# 04_MCU.net
KiCad netlist of a schematic drawn in Altium Designer
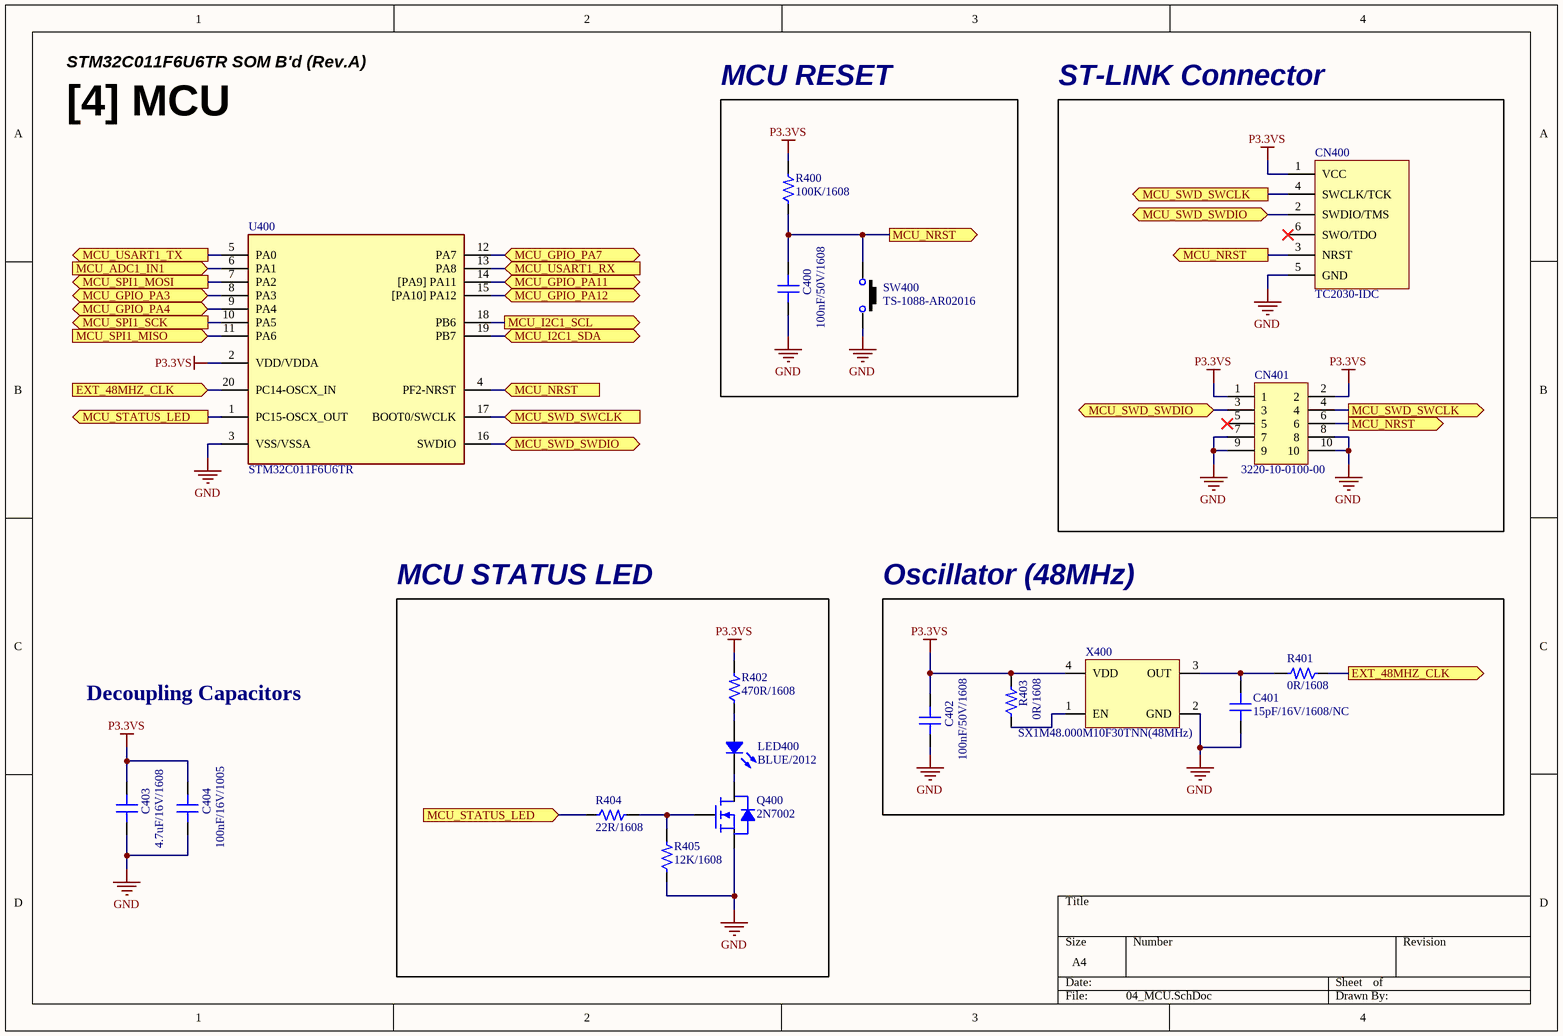
[diagram p0: 04_MCU.SchDoc]

(export (version "E")
  (design (tool "Eeschema 10.0.6"))
  (components
    (comp (ref "C400")
      (value "100nF/50V/1608")
      (footprint "CAP 1608 (0603_INCH)")
      (description "Ceramic CAP_100nF/50V/1608")
      (fields (field (name "LCSC PART #") "C14663"))
      (libsource (lib "Arkx") (part "CAP_100nF/50V/1608"))
    )
    (comp (ref "C401")
      (value "15pF/16V/1608/NC")
      (footprint "CAP 1608 (0603_INCH)/NC")
      (description "Ceramic CAP_15pF/16V/1608")
      (libsource (lib "Arkx") (part "CAP_NC_15pF/16V/1608"))
    )
    (comp (ref "C402")
      (value "100nF/50V/1608")
      (footprint "CAP 1608 (0603_INCH)")
      (description "Ceramic CAP_100nF/50V/1608")
      (fields (field (name "LCSC PART #") "C14663"))
      (libsource (lib "Arkx") (part "CAP_100nF/50V/1608"))
    )
    (comp (ref "C403")
      (value "4.7uF/16V/1608")
      (footprint "CAP 1608 (0603_INCH)")
      (description "Ceramic CAP_4.7uF/16V/1608")
      (fields (field (name "LCSC PART #") "C19666"))
      (libsource (lib "Arkx") (part "CAP_4.7uF/16V/1608"))
    )
    (comp (ref "C404")
      (value "100nF/16V/1005")
      (footprint "CAP 1005 (0402_INCH)")
      (description "Ceramic CAP_100nF/16V/1005")
      (fields (field (name "LCSC PART #") "C1525"))
      (libsource (lib "Arkx") (part "CAP_100nF/16V/1005"))
    )
    (comp (ref "CN400")
      (value "TC2030-IDC")
      (footprint "CON_TC2030-FP")
      (description "Tag-Connect No-Solder SWD Debug Connector DO NOT PLACE")
      (fields (field (name "MANUFACTURER") "Tag-Connect") (field (name "MANUFACTURER PART NUMBER") "TC2030"))
      (libsource (lib "Arkx") (part "CON_TC2030-IDC"))
    )
    (comp (ref "CN401")
      (value "3220-10-0100-00")
      (footprint "CON 3220-10-0100-00 (Hand_Solder)")
      (description "CONN HEADER VERT 10POS 1.27MM")
      (libsource (lib "Arkx") (part "CON_IDC_3220-10-0100-00"))
    )
    (comp (ref "LED400")
      (value "BLUE/2012")
      (footprint "LED MHT170RGBCT (BLUE)")
      (fields (field (name "LCSC PART #") "C2962094"))
      (libsource (lib "Arkx") (part "LED_MHT170RGBCT(BLUE)"))
    )
    (comp (ref "Q400")
      (value "2N7002")
      (footprint "SOT 23-3 (DIODES INCORPORATED)")
      (description "60V 115mA 200mW 7.5Ω@10V,500mA N Channel SOT-23  MOSFETs ROHS")
      (fields (field (name "LCSC PART #") "C8545"))
      (libsource (lib "Arkx") (part "FET_2N7002"))
    )
    (comp (ref "R400")
      (value "100K/1608")
      (footprint "RES 1608 (0603_inch)")
      (description "RES_100K/1608/0.1W")
      (fields (field (name "LCSC PART #") "C25803"))
      (libsource (lib "Arkx") (part "RES_100K/1608/0.1W"))
    )
    (comp (ref "R401")
      (value "0R/1608")
      (footprint "RES 1608 (0603_inch)")
      (description "RES_0R/1608/0.1W")
      (fields (field (name "LCSC PART #") "C21189"))
      (libsource (lib "Arkx") (part "RES_0R/1608/0.1W"))
    )
    (comp (ref "R402")
      (value "470R/1608")
      (footprint "RES 1608 (0603_inch)")
      (description "RES_470R/1608/0.1W")
      (fields (field (name "LCSC PART #") "C23179"))
      (libsource (lib "Arkx") (part "RES_470R/1608/0.1W"))
    )
    (comp (ref "R403")
      (value "0R/1608")
      (footprint "RES 1608 (0603_inch)")
      (description "RES_0R/1608/0.1W")
      (fields (field (name "LCSC PART #") "C21189"))
      (libsource (lib "Arkx") (part "RES_0R/1608/0.1W"))
    )
    (comp (ref "R404")
      (value "22R/1608")
      (footprint "RES 1608 (0603_inch)")
      (description "RES_22R/1608/0.1W")
      (fields (field (name "LCSC PART #") "C23345"))
      (libsource (lib "Arkx") (part "RES_22R/1608/0.1W"))
    )
    (comp (ref "R405")
      (value "12K/1608")
      (footprint "RES 1608 (0603_inch)")
      (description "RES_12K/1608/0.1W")
      (fields (field (name "LCSC PART #") "C22790"))
      (libsource (lib "Arkx") (part "RES_12K/1608/0.1W"))
    )
    (comp (ref "SW400")
      (value "TS-1088-AR02016")
      (footprint "SW_TS-1088-AR02016")
      (description "NO 50mA 100MΩ 100000 Times 12V 160gf@±50gf Brick nogging SPST SMD  Tactile Switches ROHS")
      (fields (field (name "LCSC PART #") "C720477"))
      (libsource (lib "Arkx") (part "SW_TS-1088-AR02016"))
    )
    (comp (ref "U400")
      (value "STM32C011F6U6TR")
      (footprint "IC_UFQFPN-20")
      (description "ARM® Cortex®-M0+ STM32C0 Microcontroller IC 32-Bit 48MHz 32KB (32K x 8) FLASH 20-UFQFPN (3x3)")
      (fields (field (name "MANUFACTURER") "STMicroelectronics") (field (name "LCSC PART #") "C5456206"))
      (libsource (lib "Arkx") (part "IC_MCU_STM32C011F6U6TR"))
    )
    (comp (ref "X400")
      (value "SX1M48.000M10F30TNN(48MHz)")
      (footprint "OSC_SMD2016-4P")
      (description "1.62V~3.63V ±10ppm CMOS 48MHz SMD2016-4P  Oscillators ROHS")
      (fields (field (name "LCSC PART #") "C2901617"))
      (libsource (lib "Arkx") (part "OSC_SX1M48.000M10F30TNN(48MHz)"))
    )
  )
  (nets
    (net (code "1") (name "/EXT_48MHZ_CLK") (class "Default")
      (node (ref "R401") (pin "1") (pinfunction "1_1") (pintype "passive"))
      (node (ref "U400") (pin "20") (pinfunction "PC14-OSCX_IN_20") (pintype "passive"))
    )
    (net (code "2") (name "/MCU_ADC1_IN1") (class "Default")
      (node (ref "U400") (pin "6") (pinfunction "PA1_6") (pintype "passive"))
    )
    (net (code "3") (name "/MCU_GPIO_PA3") (class "Default")
      (node (ref "U400") (pin "8") (pinfunction "PA3_8") (pintype "passive"))
    )
    (net (code "4") (name "/MCU_GPIO_PA4") (class "Default")
      (node (ref "U400") (pin "9") (pinfunction "PA4_9") (pintype "passive"))
    )
    (net (code "5") (name "/MCU_GPIO_PA7") (class "Default")
      (node (ref "U400") (pin "12") (pinfunction "PA7_12") (pintype "passive"))
    )
    (net (code "6") (name "/MCU_GPIO_PA11") (class "Default")
      (node (ref "U400") (pin "14") (pinfunction "[PA9]_PA11_14") (pintype "passive"))
    )
    (net (code "7") (name "/MCU_GPIO_PA12") (class "Default")
      (node (ref "U400") (pin "15") (pinfunction "[PA10]_PA12_15") (pintype "passive"))
    )
    (net (code "8") (name "/MCU_I2C1_SCL") (class "Default")
      (node (ref "U400") (pin "18") (pinfunction "PB6_18") (pintype "passive"))
    )
    (net (code "9") (name "/MCU_I2C1_SDA") (class "Default")
      (node (ref "U400") (pin "19") (pinfunction "PB7_19") (pintype "passive"))
    )
    (net (code "10") (name "/MCU_NRST") (class "Default")
      (node (ref "C400") (pin "2") (pinfunction "2_2") (pintype "passive"))
      (node (ref "CN400") (pin "3") (pinfunction "NRST_3") (pintype "passive"))
      (node (ref "CN401") (pin "6") (pinfunction "6_6") (pintype "passive"))
      (node (ref "R400") (pin "1") (pinfunction "1_1") (pintype "passive"))
      (node (ref "SW400") (pin "1") (pinfunction "1_1") (pintype "passive"))
      (node (ref "U400") (pin "4") (pinfunction "PF2-NRST_4") (pintype "passive"))
    )
    (net (code "11") (name "/MCU_SPI1_MISO") (class "Default")
      (node (ref "U400") (pin "11") (pinfunction "PA6_11") (pintype "passive"))
    )
    (net (code "12") (name "/MCU_SPI1_MOSI") (class "Default")
      (node (ref "U400") (pin "7") (pinfunction "PA2_7") (pintype "passive"))
    )
    (net (code "13") (name "/MCU_SPI1_SCK") (class "Default")
      (node (ref "U400") (pin "10") (pinfunction "PA5_10") (pintype "passive"))
    )
    (net (code "14") (name "/MCU_STATUS_LED") (class "Default")
      (node (ref "R404") (pin "1") (pinfunction "1_1") (pintype "passive"))
      (node (ref "U400") (pin "1") (pinfunction "PC15-OSCX_OUT_1") (pintype "passive"))
    )
    (net (code "15") (name "/MCU_SWD_SWCLK") (class "Default")
      (node (ref "CN400") (pin "4") (pinfunction "SWCLK/TCK_4") (pintype "passive"))
      (node (ref "CN401") (pin "4") (pinfunction "4_4") (pintype "passive"))
      (node (ref "U400") (pin "17") (pinfunction "BOOT0/SWCLK_17") (pintype "passive"))
    )
    (net (code "16") (name "/MCU_SWD_SWDIO") (class "Default")
      (node (ref "CN400") (pin "2") (pinfunction "SWDIO/TMS_2") (pintype "passive"))
      (node (ref "CN401") (pin "3") (pinfunction "3_3") (pintype "passive"))
      (node (ref "U400") (pin "16") (pinfunction "SWDIO_16") (pintype "passive"))
    )
    (net (code "17") (name "/MCU_USART1_RX") (class "Default")
      (node (ref "U400") (pin "13") (pinfunction "PA8_13") (pintype "passive"))
    )
    (net (code "18") (name "/MCU_USART1_TX") (class "Default")
      (node (ref "U400") (pin "5") (pinfunction "PA0_5") (pintype "passive"))
    )
    (net (code "19") (name "GND") (class "Default")
      (node (ref "C400") (pin "1") (pinfunction "1_1") (pintype "passive"))
      (node (ref "C401") (pin "1") (pinfunction "1_1") (pintype "passive"))
      (node (ref "C402") (pin "1") (pinfunction "1_1") (pintype "passive"))
      (node (ref "C403") (pin "1") (pinfunction "1_1") (pintype "passive"))
      (node (ref "C404") (pin "1") (pinfunction "1_1") (pintype "passive"))
      (node (ref "CN400") (pin "5") (pinfunction "GND_5") (pintype "passive"))
      (node (ref "CN401") (pin "10") (pinfunction "10_10") (pintype "passive"))
      (node (ref "CN401") (pin "7") (pinfunction "7_7") (pintype "passive"))
      (node (ref "CN401") (pin "8") (pinfunction "8_8") (pintype "passive"))
      (node (ref "CN401") (pin "9") (pinfunction "9_9") (pintype "passive"))
      (node (ref "Q400") (pin "2") (pinfunction "S_2") (pintype "passive"))
      (node (ref "R405") (pin "1") (pinfunction "1_1") (pintype "passive"))
      (node (ref "SW400") (pin "2") (pinfunction "2_2") (pintype "passive"))
      (node (ref "U400") (pin "3") (pinfunction "VSS/VSSA_3") (pintype "passive"))
      (node (ref "X400") (pin "2") (pinfunction "GND_2") (pintype "passive"))
    )
    (net (code "20") (name "Net-(LED400-BLUE)") (class "Default")
      (node (ref "LED400") (pin "3") (pinfunction "BLUE_3") (pintype "passive"))
      (node (ref "Q400") (pin "3") (pinfunction "D_3") (pintype "passive"))
    )
    (net (code "21") (name "Net-(LED400-Common_Anode)") (class "Default")
      (node (ref "LED400") (pin "4") (pinfunction "Common_Anode_4") (pintype "passive"))
      (node (ref "R402") (pin "1") (pinfunction "1_1") (pintype "passive"))
    )
    (net (code "22") (name "Net-(Q400-G)") (class "Default")
      (node (ref "Q400") (pin "1") (pinfunction "G_1") (pintype "passive"))
      (node (ref "R404") (pin "2") (pinfunction "2_2") (pintype "passive"))
      (node (ref "R405") (pin "2") (pinfunction "2_2") (pintype "passive"))
    )
    (net (code "23") (name "Net-(X400-EN)") (class "Default")
      (node (ref "R403") (pin "1") (pinfunction "1_1") (pintype "passive"))
      (node (ref "X400") (pin "1") (pinfunction "EN_1") (pintype "passive"))
    )
    (net (code "24") (name "Net-(X400-OUT)") (class "Default")
      (node (ref "C401") (pin "2") (pinfunction "2_2") (pintype "passive"))
      (node (ref "R401") (pin "2") (pinfunction "2_2") (pintype "passive"))
      (node (ref "X400") (pin "3") (pinfunction "OUT_3") (pintype "passive"))
    )
    (net (code "25") (name "P3.3VS") (class "Default")
      (node (ref "C402") (pin "2") (pinfunction "2_2") (pintype "passive"))
      (node (ref "C403") (pin "2") (pinfunction "2_2") (pintype "passive"))
      (node (ref "C404") (pin "2") (pinfunction "2_2") (pintype "passive"))
      (node (ref "CN400") (pin "1") (pinfunction "VCC_1") (pintype "passive"))
      (node (ref "CN401") (pin "1") (pinfunction "1_1") (pintype "passive"))
      (node (ref "CN401") (pin "2") (pinfunction "2_2") (pintype "passive"))
      (node (ref "R400") (pin "2") (pinfunction "2_2") (pintype "passive"))
      (node (ref "R402") (pin "2") (pinfunction "2_2") (pintype "passive"))
      (node (ref "R403") (pin "2") (pinfunction "2_2") (pintype "passive"))
      (node (ref "U400") (pin "2") (pinfunction "VDD/VDDA_2") (pintype "passive"))
      (node (ref "X400") (pin "4") (pinfunction "VDD_4") (pintype "passive"))
    )
    (net (code "26") (name "unconnected-(CN400-SWO{slash}TDO-Pad6)") (class "Default")
      (node (ref "CN400") (pin "6") (pinfunction "SWO/TDO_6") (pintype "passive+no_connect"))
    )
    (net (code "27") (name "unconnected-(CN401-Pad5)") (class "Default")
      (node (ref "CN401") (pin "5") (pinfunction "5_5") (pintype "passive+no_connect"))
    )
  )
)
